# 02_POWER_SUPPLY_USB.net
KiCad netlist of a schematic drawn in Altium Designer
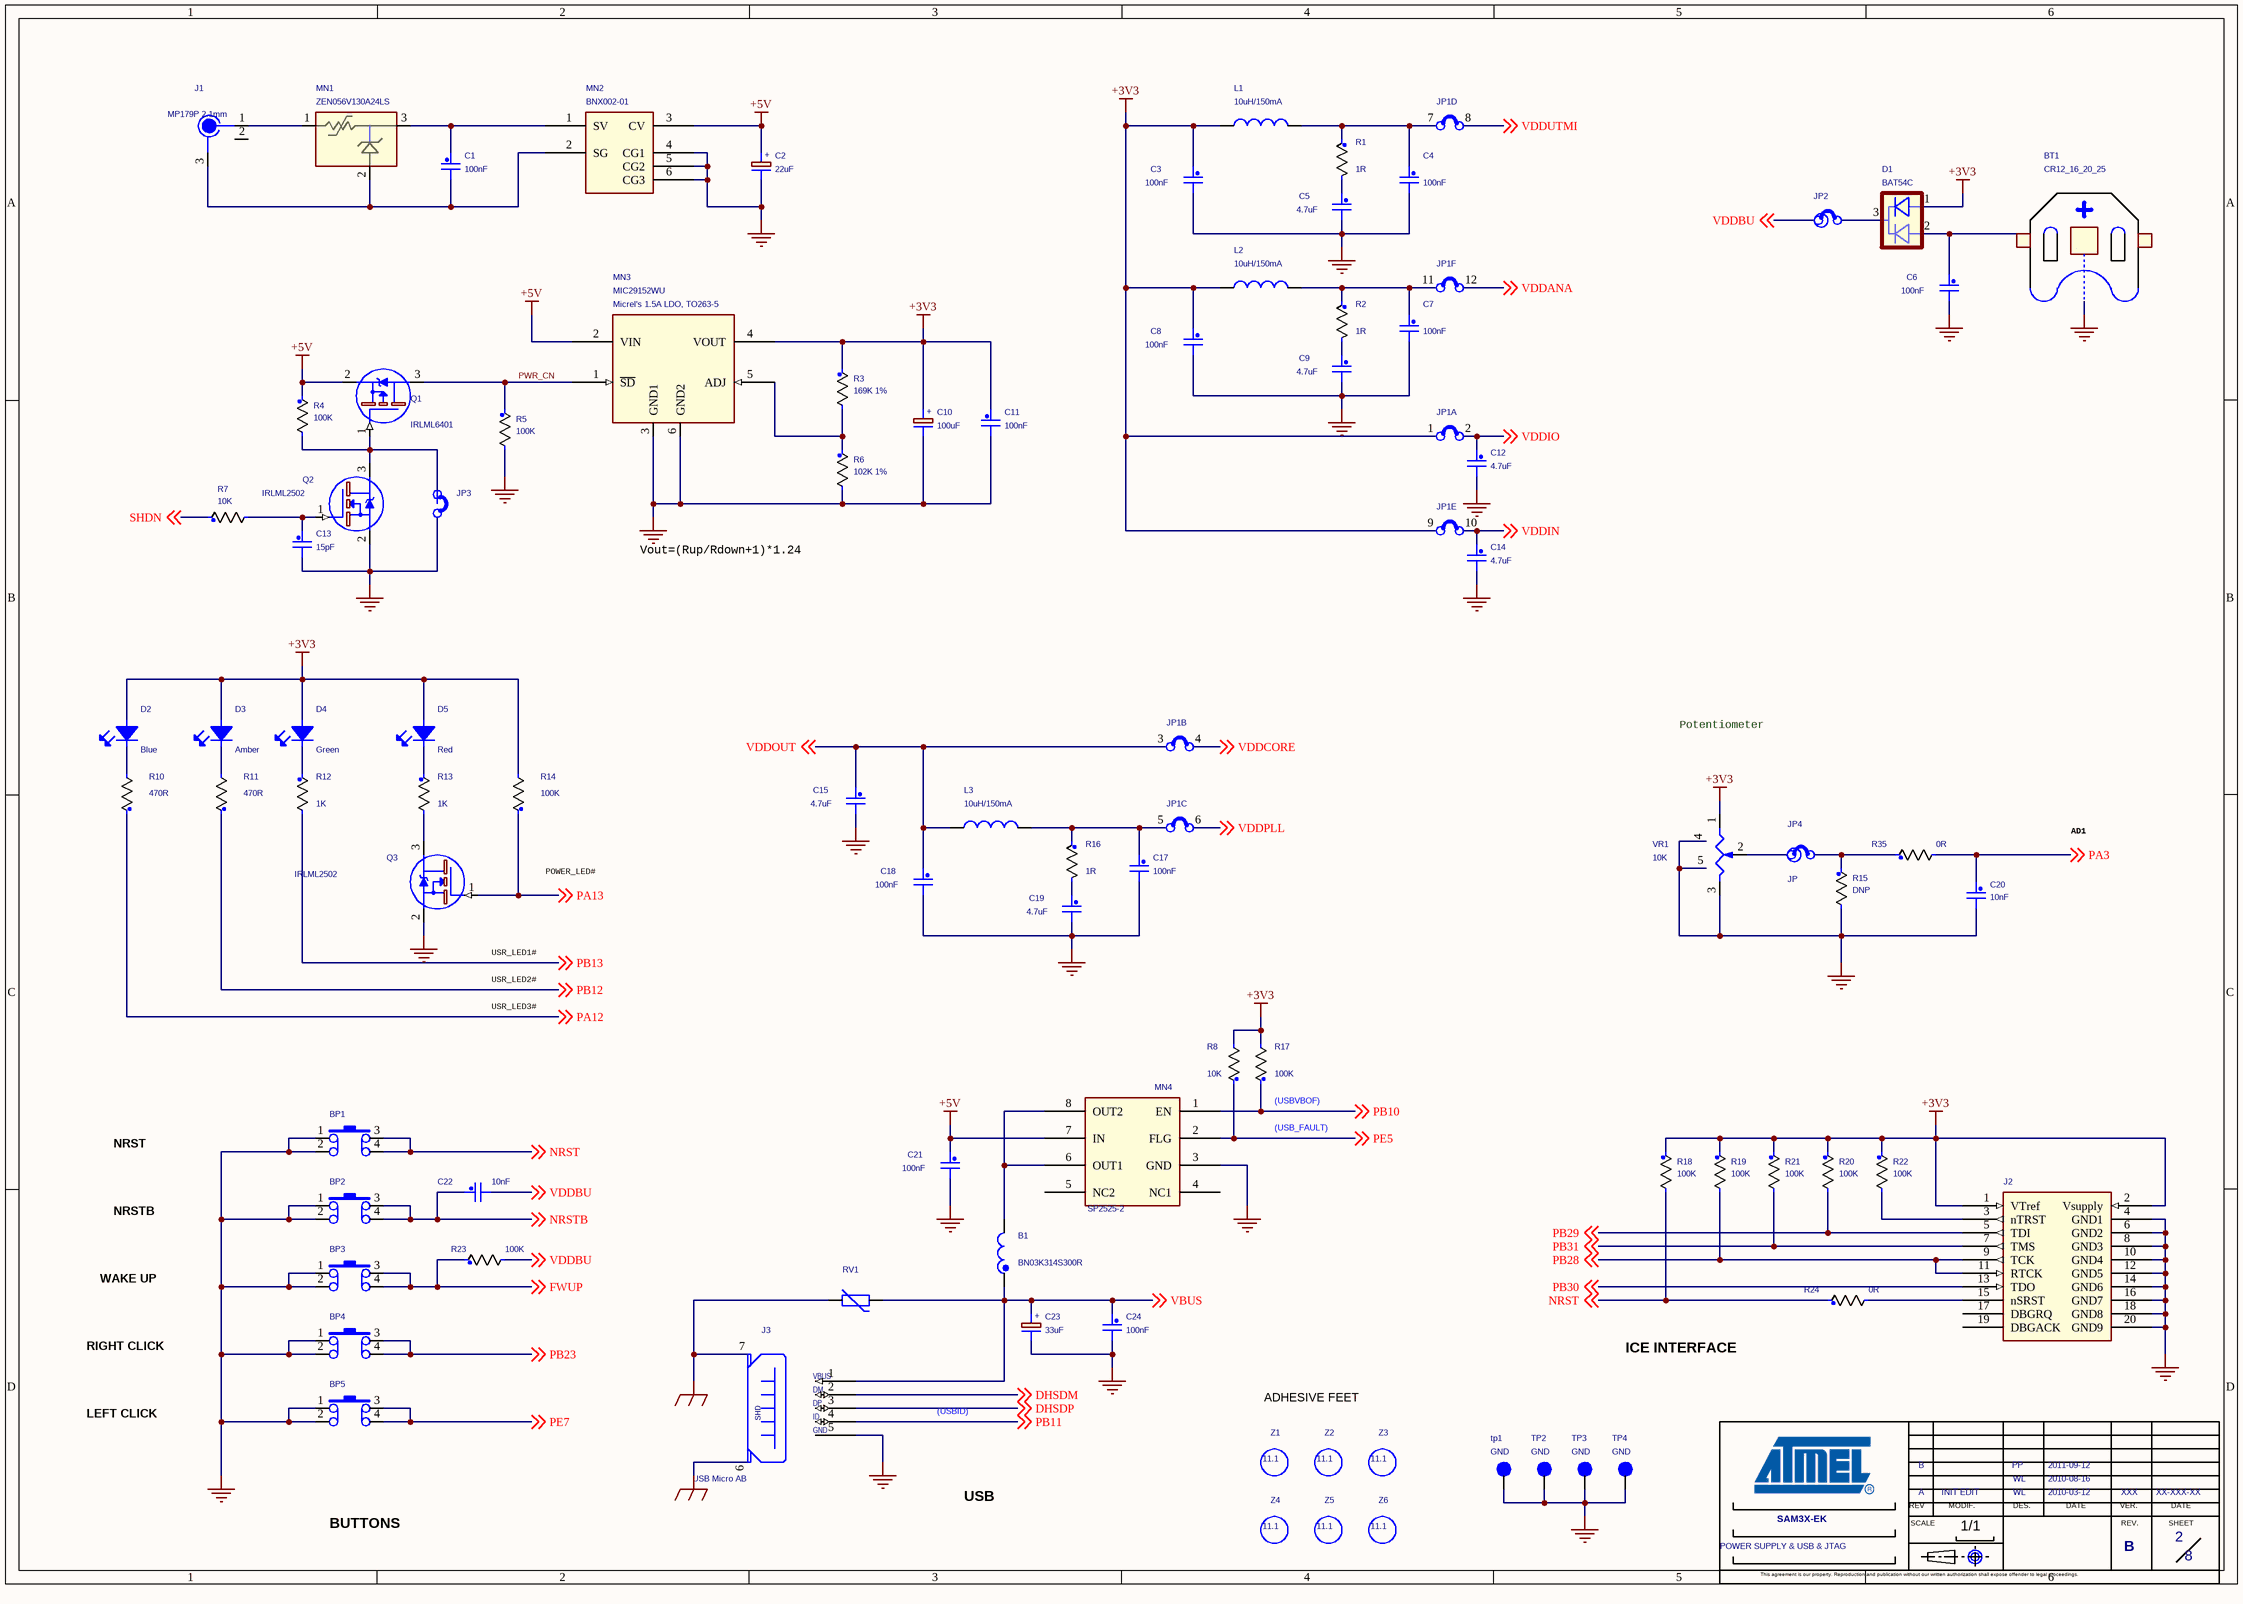
[diagram p0: 02_POWER SUPPLY & USB &.SchDoc]

(export (version "E")
  (design (tool "Eeschema 10.0.6"))
  (components
    (comp (ref "B1") (value "BN03K314S300R") (footprint "R0603") (libsource (lib "*") (part "BEAD")))
    (comp (ref "BP1") (value "T062") (footprint "KEY") (libsource (lib "*") (part "B3S_2")))
    (comp (ref "BP2") (value "T062") (footprint "KEY") (libsource (lib "*") (part "B3S_2")))
    (comp (ref "BP3") (value "T062") (footprint "KEY") (libsource (lib "*") (part "B3S_2")))
    (comp (ref "BP4") (value "T062") (footprint "KEY") (libsource (lib "*") (part "B3S_2")))
    (comp (ref "BP5") (value "T062") (footprint "KEY") (libsource (lib "*") (part "B3S_2")))
    (comp (ref "BT1")
      (value "CR12_16_20_25")
      (footprint "x-s_3000_01")
      (fields (field (name "PART NUMBER") "3UQTVB-18"))
      (libsource (lib "*") (part "Battery Holder CR12_16_20_25"))
    )
    (comp (ref "C1")
      (value "100nF")
      (footprint "CAP0805")
      (fields (field (name "VOLTAGE") "16V"))
      (libsource (lib "*") (part "C_Generic"))
    )
    (comp (ref "C2") (value "22uF") (footprint "C3528-21") (libsource (lib "*") (part "CAP_PN")))
    (comp (ref "C3")
      (value "100nF")
      (footprint "CAP0805")
      (fields (field (name "VOLTAGE") "16V"))
      (libsource (lib "*") (part "C_Generic"))
    )
    (comp (ref "C4")
      (value "100nF")
      (footprint "CAP0805")
      (fields (field (name "VOLTAGE") "16V"))
      (libsource (lib "*") (part "C_Generic"))
    )
    (comp (ref "C5")
      (value "4.7uF")
      (footprint "CAP0805")
      (fields (field (name "VOLTAGE") "16V"))
      (libsource (lib "*") (part "C_Generic"))
    )
    (comp (ref "C6")
      (value "100nF")
      (footprint "CAP0805")
      (fields (field (name "VOLTAGE") "16V"))
      (libsource (lib "*") (part "C_Generic"))
    )
    (comp (ref "C7")
      (value "100nF")
      (footprint "CAP0805")
      (fields (field (name "VOLTAGE") "16V"))
      (libsource (lib "*") (part "C_Generic"))
    )
    (comp (ref "C8")
      (value "100nF")
      (footprint "CAP0805")
      (fields (field (name "VOLTAGE") "16V"))
      (libsource (lib "*") (part "C_Generic"))
    )
    (comp (ref "C9")
      (value "4.7uF")
      (footprint "CAP0805")
      (fields (field (name "VOLTAGE") "16V"))
      (libsource (lib "*") (part "C_Generic"))
    )
    (comp (ref "C10") (value "100uF") (footprint "C3528-21") (libsource (lib "*") (part "CAP_PN")))
    (comp (ref "C11")
      (value "100nF")
      (footprint "CAP0805")
      (fields (field (name "VOLTAGE") "16V"))
      (libsource (lib "*") (part "C_Generic"))
    )
    (comp (ref "C12")
      (value "4.7uF")
      (footprint "CAP0805")
      (fields (field (name "VOLTAGE") "16V"))
      (libsource (lib "*") (part "C_Generic"))
    )
    (comp (ref "C13")
      (value "15pF")
      (footprint "CAP0805")
      (fields (field (name "VOLTAGE") "50V"))
      (libsource (lib "*") (part "C_Generic"))
    )
    (comp (ref "C14")
      (value "4.7uF")
      (footprint "CAP0805")
      (fields (field (name "VOLTAGE") "16V"))
      (libsource (lib "*") (part "C_Generic"))
    )
    (comp (ref "C15")
      (value "4.7uF")
      (footprint "CAP0805")
      (fields (field (name "VOLTAGE") "16V"))
      (libsource (lib "*") (part "C_Generic"))
    )
    (comp (ref "C17")
      (value "100nF")
      (footprint "CAP0805")
      (fields (field (name "VOLTAGE") "16V"))
      (libsource (lib "*") (part "C_Generic"))
    )
    (comp (ref "C18")
      (value "100nF")
      (footprint "CAP0805")
      (fields (field (name "VOLTAGE") "16V"))
      (libsource (lib "*") (part "C_Generic"))
    )
    (comp (ref "C19")
      (value "4.7uF")
      (footprint "CAP0805")
      (fields (field (name "VOLTAGE") "16V"))
      (libsource (lib "*") (part "C_Generic"))
    )
    (comp (ref "C20")
      (value "10nF")
      (footprint "CAP0805")
      (fields (field (name "VOLTAGE") "16V"))
      (libsource (lib "*") (part "C_Generic"))
    )
    (comp (ref "C21")
      (value "100nF")
      (footprint "CAP0805")
      (fields (field (name "VOLTAGE") "16V"))
      (libsource (lib "*") (part "C_Generic"))
    )
    (comp (ref "C22")
      (value "10nF")
      (footprint "CAP0805")
      (fields (field (name "VOLTAGE") "16V"))
      (libsource (lib "*") (part "C_Generic"))
    )
    (comp (ref "C23") (value "33uF") (footprint "C3528-21") (libsource (lib "*") (part "CAP_PN")))
    (comp (ref "C24")
      (value "100nF")
      (footprint "CAP0805")
      (fields (field (name "VOLTAGE") "16V"))
      (libsource (lib "*") (part "C_Generic"))
    )
    (comp (ref "D1") (value "BAT54C") (footprint "SOT-23") (libsource (lib "*") (part "BAT54C")))
    (comp (ref "D2") (value "Blue") (footprint "LED0805") (libsource (lib "*") (part "LED_Small_1")))
    (comp (ref "D3") (value "Amber") (footprint "LED0805") (libsource (lib "*") (part "LED_Small_1")))
    (comp (ref "D4") (value "Green") (footprint "LED0805") (libsource (lib "*") (part "LED_Small_1")))
    (comp (ref "D5") (value "Red") (footprint "LED0805") (libsource (lib "*") (part "LED_Small_1")))
    (comp (ref "J1")
      (value "Jack MP179P 2.1mm")
      (footprint "CONNECT3PTS03")
      (fields (field (name "VAL") "MP179P 2.1mm"))
      (libsource (lib "*") (part "Jack"))
    )
    (comp (ref "J2") (value "IDC20-2.54mm") (footprint "20PIN2") (libsource (lib "*") (part "JTAG")))
    (comp (ref "J3")
      (value "USB Micro AB")
      (footprint "usb_micro_ab")
      (description "CON,USB Micro B")
      (fields (field (name "MANUFACTURER PART NUMBER") "1981568-1") (field (name "MANUFACTURER") "Tyco"))
      (libsource (lib "*") (part "USB_MicroAB"))
    )
    (comp (ref "JP1")
      (value "SMT_JUMPER")
      (footprint "jms_tsm-2x6pts")
      (libsource (lib "*") (part "SMT_JUMPER"))
    )
    (comp (ref "JP2") (value "JP") (footprint "BAR2PTS02") (libsource (lib "*") (part "JUMP_0")))
    (comp (ref "JP3") (value "JP") (footprint "BAR2PTS02") (libsource (lib "*") (part "JUMP_0")))
    (comp (ref "JP4") (value "JP") (footprint "BAR2PTS02") (libsource (lib "*") (part "JUMP_0")))
    (comp (ref "L1") (value "10uH/150mA") (footprint "NLFV25T") (libsource (lib "*") (part "L_0")))
    (comp (ref "L2") (value "10uH/150mA") (footprint "NLFV25T") (libsource (lib "*") (part "L_0")))
    (comp (ref "L3") (value "10uH/150mA") (footprint "NLFV25T") (libsource (lib "*") (part "L_0")))
    (comp (ref "MN1") (value "ZEN056V130A24LS") (footprint "POLYZEN") (libsource (lib "*") (part "ZEN056")))
    (comp (ref "MN2") (value "BNX002-01") (footprint "BNX001") (libsource (lib "*") (part "BNX002_01")))
    (comp (ref "MN3")
      (value "MIC29152WU")
      (footprint "ADI/SM/TO263/5")
      (fields (field (name "NOTE") "Micrel's 1.5A LDO, TO263-5"))
      (libsource (lib "*") (part "LP3965ES_ADJ"))
    )
    (comp (ref "MN4") (value "SP2525-2") (footprint "NSOIC8") (libsource (lib "*") (part "SP2525-SO8_1")))
    (comp (ref "Q1")
      (value "IRLML6401")
      (footprint "SOT23T02")
      (fields (field (name "REF") "IRLML6401"))
      (libsource (lib "*") (part "IRLML6302"))
    )
    (comp (ref "Q2")
      (value "IRLML2502")
      (footprint "SOT23T02")
      (fields (field (name "VAL") "IRLML2502"))
      (libsource (lib "") (part "IRLML2402_1"))
    )
    (comp (ref "Q3")
      (value "IRLML2502")
      (footprint "SOT23T02")
      (fields (field (name "VAL") "IRLML2502"))
      (libsource (lib "*") (part "IRLML2402"))
    )
    (comp (ref "R1") (value "1R") (footprint "R0603") (libsource (lib "*") (part "R_Generic")))
    (comp (ref "R2") (value "1R") (footprint "R0603") (libsource (lib "*") (part "R_Generic")))
    (comp (ref "R3") (value "169K 1%") (footprint "r0603") (libsource (lib "*") (part "R_Generic")))
    (comp (ref "R4") (value "100K") (footprint "R0603") (libsource (lib "*") (part "R_Generic")))
    (comp (ref "R5") (value "100K") (footprint "R0603") (libsource (lib "*") (part "R_Generic")))
    (comp (ref "R6") (value "102K 1%") (footprint "r0603") (libsource (lib "*") (part "R_Generic")))
    (comp (ref "R7") (value "10K") (footprint "R0603") (libsource (lib "*") (part "R_Generic")))
    (comp (ref "R8") (value "10K") (footprint "R0603") (libsource (lib "*") (part "R_Generic")))
    (comp (ref "R10") (value "470R") (footprint "R0603") (libsource (lib "*") (part "R_Generic")))
    (comp (ref "R11") (value "470R") (footprint "R0603") (libsource (lib "*") (part "R_Generic")))
    (comp (ref "R12") (value "1K") (footprint "r0603") (libsource (lib "*") (part "R_Generic")))
    (comp (ref "R13") (value "1K") (footprint "r0603") (libsource (lib "*") (part "R_Generic")))
    (comp (ref "R14") (value "100K") (footprint "R0603") (libsource (lib "*") (part "R_Generic")))
    (comp (ref "R15") (value "DNP") (footprint "R0603") (libsource (lib "*") (part "R_Generic")))
    (comp (ref "R16") (value "1R") (footprint "R0603") (libsource (lib "*") (part "R_Generic")))
    (comp (ref "R17") (value "100K") (footprint "R0603") (libsource (lib "*") (part "R_Generic")))
    (comp (ref "R18") (value "100K") (footprint "r0603") (libsource (lib "*") (part "R_Generic")))
    (comp (ref "R19") (value "100K") (footprint "r0603") (libsource (lib "*") (part "R_Generic")))
    (comp (ref "R20") (value "100K") (footprint "r0603") (libsource (lib "*") (part "R_Generic")))
    (comp (ref "R21") (value "100K") (footprint "r0603") (libsource (lib "*") (part "R_Generic")))
    (comp (ref "R22") (value "100K") (footprint "r0603") (libsource (lib "*") (part "R_Generic")))
    (comp (ref "R23") (value "100K") (footprint "R0603") (libsource (lib "*") (part "R_Generic")))
    (comp (ref "R24") (value "0R") (footprint "r0603") (libsource (lib "*") (part "R_Generic")))
    (comp (ref "R35") (value "0R") (footprint "r0603") (libsource (lib "*") (part "R_Generic")))
    (comp (ref "RV1")
      (value "VARISTOR_0603")
      (footprint "R0603")
      (libsource (lib "*") (part "VARISTOR_0603"))
    )
    (comp (ref "SH1")
      (value "Jumper Pitch 2.54")
      (footprint "JUMPER-2.54")
      (description "Jumper,2 Points Jumper Pitch 2.54")
      (fields (field (name "PART NUMBER") "440-00002-1") (field (name "MANUFACTURER") "WIESON"))
      (libsource (lib "") (part "JUMPER-2.54_1"))
    )
    (comp (ref "SH2")
      (value "Jumper Pitch 2.54")
      (footprint "JUMPER-2.54")
      (description "Jumper,2 Points Jumper Pitch 2.54")
      (fields (field (name "PART NUMBER") "440-00002-1") (field (name "MANUFACTURER") "WIESON"))
      (libsource (lib "*") (part "JUMPER-2.54"))
    )
    (comp (ref "SH3")
      (value "Jumper Pitch 2.54")
      (footprint "JUMPER-2.54")
      (description "Jumper,2 Points Jumper Pitch 2.54")
      (fields (field (name "PART NUMBER") "440-00002-1") (field (name "MANUFACTURER") "WIESON"))
      (libsource (lib "") (part "JUMPER-2.54_1"))
    )
    (comp (ref "SH4")
      (value "Jumper Pitch 2.54")
      (footprint "JUMPER-2.54")
      (description "Jumper,2 Points Jumper Pitch 2.54")
      (fields
        (field (name "MANUFACTURER PART NUMBER") "G4160-1A60BF1U")
        (field (name "MANUFACTURER") "WIESON")
      )
      (libsource (lib "") (part "JUMPER-2.54_1"))
    )
    (comp (ref "SH5")
      (value "Jumper Pitch 2.54")
      (footprint "JUMPER-2.54")
      (description "Jumper,2 Points Jumper Pitch 2.54")
      (fields (field (name "PART NUMBER") "440-00002-1") (field (name "MANUFACTURER") "WIESON"))
      (libsource (lib "") (part "JUMPER-2.54_1"))
    )
    (comp (ref "SH6")
      (value "Jumper Pitch 2.54")
      (footprint "JUMPER-2.54")
      (description "Jumper,2 Points Jumper Pitch 2.54")
      (fields (field (name "PART NUMBER") "440-00002-1") (field (name "MANUFACTURER") "WIESON"))
      (libsource (lib "") (part "JUMPER-2.54_1"))
    )
    (comp (ref "SH8")
      (value "Jumper Pitch 2.54")
      (footprint "JUMPER-2.54")
      (description "Jumper,2 Points Jumper Pitch 2.54")
      (fields (field (name "PART NUMBER") "440-00002-1") (field (name "MANUFACTURER") "WIESON"))
      (libsource (lib "") (part "JUMPER-2.54_1"))
    )
    (comp (ref "SH9")
      (value "Jumper Pitch 2.54")
      (footprint "JUMPER-2.54")
      (description "Jumper,2 Points Jumper Pitch 2.54")
      (fields
        (field (name "MANUFACTURER PART NUMBER") "G4160-1A60BF1U")
        (field (name "MANUFACTURER") "WIESON")
      )
      (libsource (lib "*") (part "JUMPER-2.54"))
    )
    (comp (ref "SH10")
      (value "Jumper Pitch 2.54")
      (footprint "JUMPER-2.54")
      (description "Jumper,2 Points Jumper Pitch 2.54")
      (fields (field (name "PART NUMBER") "440-00002-1") (field (name "MANUFACTURER") "WIESON"))
      (libsource (lib "") (part "JUMPER-2.54_1"))
    )
    (comp (ref "tp1") (value "GND") (footprint "KST5012") (libsource (lib "*") (part "TP")))
    (comp (ref "TP2") (value "GND") (footprint "KST5012") (libsource (lib "*") (part "TP")))
    (comp (ref "TP3") (value "GND") (footprint "KST5012") (libsource (lib "*") (part "TP")))
    (comp (ref "TP4") (value "GND") (footprint "KST5012") (libsource (lib "*") (part "TP")))
    (comp (ref "VR1") (value "10K") (footprint "POT_3") (libsource (lib "*") (part "POT2")))
    (comp (ref "Z1")
      (value "11.1")
      (footprint "TM6CIR3_2")
      (libsource (lib "*") (part "PIED ADHESIF 11.1mm"))
    )
    (comp (ref "Z2")
      (value "11.1")
      (footprint "TM6CIR3_2")
      (libsource (lib "*") (part "PIED ADHESIF 11.1mm"))
    )
    (comp (ref "Z3")
      (value "11.1")
      (footprint "TM6CIR3_2")
      (libsource (lib "*") (part "PIED ADHESIF 11.1mm"))
    )
    (comp (ref "Z4")
      (value "11.1")
      (footprint "TM6CIR3_2")
      (libsource (lib "*") (part "PIED ADHESIF 11.1mm"))
    )
    (comp (ref "Z5")
      (value "11.1")
      (footprint "TM6CIR3_2")
      (libsource (lib "*") (part "PIED ADHESIF 11.1mm"))
    )
    (comp (ref "Z6")
      (value "11.1")
      (footprint "TM6CIR3_2")
      (libsource (lib "*") (part "PIED ADHESIF 11.1mm"))
    )
  )
  (nets
    (net (code "1") (name "+3V3") (class "Default")
      (node (ref "C10") (pin "1") (pinfunction "1_1") (pintype "passive"))
      (node (ref "C11") (pin "1") (pinfunction "1_1") (pintype "passive"))
      (node (ref "C3") (pin "1") (pinfunction "1_1") (pintype "passive"))
      (node (ref "C8") (pin "1") (pinfunction "1_1") (pintype "passive"))
      (node (ref "D1") (pin "1") (pinfunction "K_1") (pintype "passive"))
      (node (ref "D2") (pin "1") (pinfunction "A_1") (pintype "passive"))
      (node (ref "D3") (pin "1") (pinfunction "A_1") (pintype "passive"))
      (node (ref "D4") (pin "1") (pinfunction "A_1") (pintype "passive"))
      (node (ref "D5") (pin "1") (pinfunction "A_1") (pintype "passive"))
      (node (ref "J2") (pin "1") (pinfunction "VTref_1") (pintype "input"))
      (node (ref "J2") (pin "2") (pinfunction "Vsupply_2") (pintype "input"))
      (node (ref "JP1") (pin "1") (pinfunction "1_1") (pintype "passive"))
      (node (ref "JP1") (pin "9") (pinfunction "9_9") (pintype "passive"))
      (node (ref "L1") (pin "2") (pinfunction "2_2") (pintype "passive"))
      (node (ref "L2") (pin "2") (pinfunction "2_2") (pintype "passive"))
      (node (ref "MN3") (pin "4") (pinfunction "VOUT_4") (pintype "power_in"))
      (node (ref "R14") (pin "2") (pinfunction "2_2") (pintype "passive"))
      (node (ref "R17") (pin "2") (pinfunction "2_2") (pintype "passive"))
      (node (ref "R18") (pin "1") (pinfunction "1_1") (pintype "passive"))
      (node (ref "R19") (pin "1") (pinfunction "1_1") (pintype "passive"))
      (node (ref "R20") (pin "1") (pinfunction "1_1") (pintype "passive"))
      (node (ref "R21") (pin "1") (pinfunction "1_1") (pintype "passive"))
      (node (ref "R22") (pin "1") (pinfunction "1_1") (pintype "passive"))
      (node (ref "R3") (pin "1") (pinfunction "1_1") (pintype "passive"))
      (node (ref "R8") (pin "2") (pinfunction "2_2") (pintype "passive"))
      (node (ref "VR1") (pin "1") (pinfunction "1_1") (pintype "passive"))
    )
    (net (code "2") (name "+5V") (class "Default")
      (node (ref "C2") (pin "1") (pinfunction "1_1") (pintype "passive"))
      (node (ref "C21") (pin "1") (pinfunction "1_1") (pintype "passive"))
      (node (ref "MN2") (pin "3") (pinfunction "CV_3") (pintype "passive"))
      (node (ref "MN3") (pin "2") (pinfunction "VIN_2") (pintype "power_in"))
      (node (ref "MN4") (pin "7") (pinfunction "IN_7") (pintype "power_in"))
      (node (ref "Q1") (pin "2") (pinfunction "S_2") (pintype "passive"))
      (node (ref "R4") (pin "1") (pinfunction "1_1") (pintype "passive"))
    )
    (net (code "3") (name "/PWR_CN") (class "Default")
      (node (ref "MN3") (pin "1") (pinfunction "~{SD}_1") (pintype "input"))
      (node (ref "Q1") (pin "3") (pinfunction "D_3") (pintype "open_collector"))
      (node (ref "R5") (pin "1") (pinfunction "1_1") (pintype "passive"))
    )
    (net (code "4") (name "DHSDM") (class "Default")
      (node (ref "J3") (pin "2") (pinfunction "DM_2") (pintype "bidirectional"))
    )
    (net (code "5") (name "DHSDP") (class "Default")
      (node (ref "J3") (pin "3") (pinfunction "DP_3") (pintype "bidirectional"))
    )
    (net (code "6") (name "FWUP") (class "Default")
      (node (ref "BP3") (pin "3") (pinfunction "T3_3") (pintype "passive"))
      (node (ref "BP3") (pin "4") (pinfunction "T4_4") (pintype "passive"))
      (node (ref "R23") (pin "1") (pinfunction "1_1") (pintype "passive"))
    )
    (net (code "7") (name "GND_EARTH") (class "Default")
      (node (ref "J3") (pin "6") (pinfunction "SH1_6") (pintype "passive"))
      (node (ref "J3") (pin "7") (pinfunction "SH2_7") (pintype "passive"))
      (node (ref "RV1") (pin "1") (pinfunction "1_1") (pintype "passive"))
    )
    (net (code "8") (name "GND_POWER") (class "Default")
      (node (ref "BP1") (pin "1") (pinfunction "T1_1") (pintype "passive"))
      (node (ref "BP1") (pin "2") (pinfunction "T2_2") (pintype "passive"))
      (node (ref "BP2") (pin "1") (pinfunction "T1_1") (pintype "passive"))
      (node (ref "BP2") (pin "2") (pinfunction "T2_2") (pintype "passive"))
      (node (ref "BP3") (pin "1") (pinfunction "T1_1") (pintype "passive"))
      (node (ref "BP3") (pin "2") (pinfunction "T2_2") (pintype "passive"))
      (node (ref "BP4") (pin "1") (pinfunction "T1_1") (pintype "passive"))
      (node (ref "BP4") (pin "2") (pinfunction "T2_2") (pintype "passive"))
      (node (ref "BP5") (pin "1") (pinfunction "T1_1") (pintype "passive"))
      (node (ref "BP5") (pin "2") (pinfunction "T2_2") (pintype "passive"))
      (node (ref "BT1") (pin "1") (pinfunction "M_1") (pintype "passive"))
      (node (ref "C10") (pin "2") (pinfunction "2_2") (pintype "passive"))
      (node (ref "C11") (pin "2") (pinfunction "2_2") (pintype "passive"))
      (node (ref "C12") (pin "2") (pinfunction "2_2") (pintype "passive"))
      (node (ref "C13") (pin "2") (pinfunction "2_2") (pintype "passive"))
      (node (ref "C14") (pin "2") (pinfunction "2_2") (pintype "passive"))
      (node (ref "C15") (pin "2") (pinfunction "2_2") (pintype "passive"))
      (node (ref "C17") (pin "2") (pinfunction "2_2") (pintype "passive"))
      (node (ref "C18") (pin "2") (pinfunction "2_2") (pintype "passive"))
      (node (ref "C19") (pin "2") (pinfunction "2_2") (pintype "passive"))
      (node (ref "C2") (pin "2") (pinfunction "2_2") (pintype "passive"))
      (node (ref "C20") (pin "2") (pinfunction "2_2") (pintype "passive"))
      (node (ref "C21") (pin "2") (pinfunction "2_2") (pintype "passive"))
      (node (ref "C23") (pin "2") (pinfunction "2_2") (pintype "passive"))
      (node (ref "C24") (pin "2") (pinfunction "2_2") (pintype "passive"))
      (node (ref "C3") (pin "2") (pinfunction "2_2") (pintype "passive"))
      (node (ref "C4") (pin "2") (pinfunction "2_2") (pintype "passive"))
      (node (ref "C5") (pin "2") (pinfunction "2_2") (pintype "passive"))
      (node (ref "C6") (pin "2") (pinfunction "2_2") (pintype "passive"))
      (node (ref "C7") (pin "2") (pinfunction "2_2") (pintype "passive"))
      (node (ref "C8") (pin "2") (pinfunction "2_2") (pintype "passive"))
      (node (ref "C9") (pin "2") (pinfunction "2_2") (pintype "passive"))
      (node (ref "J2") (pin "10") (pinfunction "GND4_10") (pintype "power_in"))
      (node (ref "J2") (pin "12") (pinfunction "GND5_12") (pintype "power_in"))
      (node (ref "J2") (pin "14") (pinfunction "GND6_14") (pintype "power_in"))
      (node (ref "J2") (pin "16") (pinfunction "GND7_16") (pintype "power_in"))
      (node (ref "J2") (pin "18") (pinfunction "GND8_18") (pintype "power_in"))
      (node (ref "J2") (pin "20") (pinfunction "GND9_20") (pintype "power_in"))
      (node (ref "J2") (pin "4") (pinfunction "GND1_4") (pintype "power_in"))
      (node (ref "J2") (pin "6") (pinfunction "GND2_6") (pintype "power_in"))
      (node (ref "J2") (pin "8") (pinfunction "GND3_8") (pintype "power_in"))
      (node (ref "J3") (pin "5") (pinfunction "GND_5") (pintype "power_in"))
      (node (ref "JP3") (pin "2") (pinfunction "2_2") (pintype "passive"))
      (node (ref "MN2") (pin "4") (pinfunction "CG1_4") (pintype "passive"))
      (node (ref "MN2") (pin "5") (pinfunction "CG2_5") (pintype "passive"))
      (node (ref "MN2") (pin "6") (pinfunction "CG3_6") (pintype "passive"))
      (node (ref "MN3") (pin "3") (pinfunction "GND1_3") (pintype "power_in"))
      (node (ref "MN3") (pin "6") (pinfunction "GND2_6") (pintype "power_in"))
      (node (ref "MN4") (pin "3") (pinfunction "GND_3") (pintype "passive"))
      (node (ref "Q2") (pin "2") (pinfunction "S_2") (pintype "passive"))
      (node (ref "Q3") (pin "2") (pinfunction "S_2") (pintype "passive"))
      (node (ref "R15") (pin "2") (pinfunction "2_2") (pintype "passive"))
      (node (ref "R5") (pin "2") (pinfunction "2_2") (pintype "passive"))
      (node (ref "R6") (pin "2") (pinfunction "2_2") (pintype "passive"))
      (node (ref "TP2") (pin "1") (pinfunction "TP_1") (pintype "passive"))
      (node (ref "TP3") (pin "1") (pinfunction "TP_1") (pintype "passive"))
      (node (ref "TP4") (pin "1") (pinfunction "TP_1") (pintype "passive"))
      (node (ref "VR1") (pin "3") (pinfunction "3_3") (pintype "passive"))
      (node (ref "VR1") (pin "4") (pinfunction "4_4") (pintype "passive"))
      (node (ref "VR1") (pin "5") (pinfunction "5_5") (pintype "passive"))
      (node (ref "tp1") (pin "1") (pinfunction "TP_1") (pintype "passive"))
    )
    (net (code "9") (name "NRST") (class "Default")
      (node (ref "BP1") (pin "3") (pinfunction "T3_3") (pintype "passive"))
      (node (ref "BP1") (pin "4") (pinfunction "T4_4") (pintype "passive"))
      (node (ref "R18") (pin "2") (pinfunction "2_2") (pintype "passive"))
      (node (ref "R24") (pin "1") (pinfunction "1_1") (pintype "passive"))
    )
    (net (code "10") (name "NRSTB") (class "Default")
      (node (ref "BP2") (pin "3") (pinfunction "T3_3") (pintype "passive"))
      (node (ref "BP2") (pin "4") (pinfunction "T4_4") (pintype "passive"))
      (node (ref "C22") (pin "1") (pinfunction "1_1") (pintype "passive"))
    )
    (net (code "11") (name "Net-(BT1-P1)") (class "Default")
      (node (ref "BT1") (pin "2") (pinfunction "P1_2") (pintype "passive"))
      (node (ref "C6") (pin "1") (pinfunction "1_1") (pintype "passive"))
      (node (ref "D1") (pin "2") (pinfunction "A_2") (pintype "passive"))
    )
    (net (code "12") (name "Net-(C4-Pad1)") (class "Default")
      (node (ref "C4") (pin "1") (pinfunction "1_1") (pintype "passive"))
      (node (ref "JP1") (pin "7") (pinfunction "7_7") (pintype "passive"))
      (node (ref "L1") (pin "1") (pinfunction "1_1") (pintype "passive"))
      (node (ref "R1") (pin "1") (pinfunction "1_1") (pintype "passive"))
    )
    (net (code "13") (name "Net-(C5-Pad1)") (class "Default")
      (node (ref "C5") (pin "1") (pinfunction "1_1") (pintype "passive"))
      (node (ref "R1") (pin "2") (pinfunction "2_2") (pintype "passive"))
    )
    (net (code "14") (name "Net-(C7-Pad1)") (class "Default")
      (node (ref "C7") (pin "1") (pinfunction "1_1") (pintype "passive"))
      (node (ref "JP1") (pin "11") (pinfunction "11_11") (pintype "passive"))
      (node (ref "L2") (pin "1") (pinfunction "1_1") (pintype "passive"))
      (node (ref "R2") (pin "1") (pinfunction "1_1") (pintype "passive"))
    )
    (net (code "15") (name "Net-(C9-Pad1)") (class "Default")
      (node (ref "C9") (pin "1") (pinfunction "1_1") (pintype "passive"))
      (node (ref "R2") (pin "2") (pinfunction "2_2") (pintype "passive"))
    )
    (net (code "16") (name "Net-(C17-Pad1)") (class "Default")
      (node (ref "C17") (pin "1") (pinfunction "1_1") (pintype "passive"))
      (node (ref "JP1") (pin "5") (pinfunction "5_5") (pintype "passive"))
      (node (ref "L3") (pin "1") (pinfunction "1_1") (pintype "passive"))
      (node (ref "R16") (pin "1") (pinfunction "1_1") (pintype "passive"))
    )
    (net (code "17") (name "Net-(C19-Pad1)") (class "Default")
      (node (ref "C19") (pin "1") (pinfunction "1_1") (pintype "passive"))
      (node (ref "R16") (pin "2") (pinfunction "2_2") (pintype "passive"))
    )
    (net (code "18") (name "Net-(D1-COM)") (class "Default")
      (node (ref "D1") (pin "3") (pinfunction "COM_3") (pintype "passive"))
      (node (ref "JP2") (pin "2") (pinfunction "2_2") (pintype "passive"))
    )
    (net (code "19") (name "Net-(D2-K)") (class "Default")
      (node (ref "D2") (pin "2") (pinfunction "K_2") (pintype "passive"))
      (node (ref "R10") (pin "2") (pinfunction "2_2") (pintype "passive"))
    )
    (net (code "20") (name "Net-(D3-K)") (class "Default")
      (node (ref "D3") (pin "2") (pinfunction "K_2") (pintype "passive"))
      (node (ref "R11") (pin "2") (pinfunction "2_2") (pintype "passive"))
    )
    (net (code "21") (name "Net-(D4-K)") (class "Default")
      (node (ref "D4") (pin "2") (pinfunction "K_2") (pintype "passive"))
      (node (ref "R12") (pin "1") (pinfunction "1_1") (pintype "passive"))
    )
    (net (code "22") (name "Net-(D5-K)") (class "Default")
      (node (ref "D5") (pin "2") (pinfunction "K_2") (pintype "passive"))
      (node (ref "R13") (pin "1") (pinfunction "1_1") (pintype "passive"))
    )
    (net (code "23") (name "Net-(J2-nSRST)") (class "Default")
      (node (ref "J2") (pin "15") (pinfunction "nSRST_15") (pintype "passive"))
      (node (ref "R24") (pin "2") (pinfunction "2_2") (pintype "passive"))
    )
    (net (code "24") (name "Net-(J2-nTRST)") (class "Default")
      (node (ref "J2") (pin "3") (pinfunction "nTRST_3") (pintype "output"))
      (node (ref "R22") (pin "2") (pinfunction "2_2") (pintype "passive"))
    )
    (net (code "25") (name "Net-(JP4-Pad1)") (class "Default")
      (node (ref "JP4") (pin "1") (pinfunction "1_1") (pintype "passive"))
      (node (ref "VR1") (pin "2") (pinfunction "2_2") (pintype "passive"))
    )
    (net (code "26") (name "Net-(JP4-Pad2)") (class "Default")
      (node (ref "JP4") (pin "2") (pinfunction "2_2") (pintype "passive"))
      (node (ref "R15") (pin "1") (pinfunction "1_1") (pintype "passive"))
      (node (ref "R35") (pin "1") (pinfunction "1_1") (pintype "passive"))
    )
    (net (code "27") (name "Net-(MN1-GND)") (class "Default")
      (node (ref "C1") (pin "2") (pinfunction "2_2") (pintype "passive"))
      (node (ref "J1") (pin "3") (pinfunction "3_3") (pintype "passive"))
      (node (ref "MN1") (pin "2") (pinfunction "GND_2") (pintype "passive"))
      (node (ref "MN2") (pin "2") (pinfunction "SG_2") (pintype "passive"))
    )
    (net (code "28") (name "Net-(MN1-VIN)") (class "Default")
      (node (ref "J1") (pin "1") (pinfunction "1_1") (pintype "passive"))
      (node (ref "MN1") (pin "1") (pinfunction "VIN_1") (pintype "passive"))
    )
    (net (code "29") (name "Net-(MN1-VOUT)") (class "Default")
      (node (ref "C1") (pin "1") (pinfunction "1_1") (pintype "passive"))
      (node (ref "MN1") (pin "3") (pinfunction "VOUT_3") (pintype "passive"))
      (node (ref "MN2") (pin "1") (pinfunction "SV_1") (pintype "passive"))
    )
    (net (code "30") (name "Net-(MN3-ADJ)") (class "Default")
      (node (ref "MN3") (pin "5") (pinfunction "ADJ_5") (pintype "input"))
      (node (ref "R3") (pin "2") (pinfunction "2_2") (pintype "passive"))
      (node (ref "R6") (pin "1") (pinfunction "1_1") (pintype "passive"))
    )
    (net (code "31") (name "Net-(MN4-OUT1)") (class "Default")
      (node (ref "B1") (pin "2") (pinfunction "2_2") (pintype "passive"))
      (node (ref "MN4") (pin "6") (pinfunction "OUT1_6") (pintype "passive"))
      (node (ref "MN4") (pin "8") (pinfunction "OUT2_8") (pintype "passive"))
    )
    (net (code "32") (name "Net-(Q1-G)") (class "Default")
      (node (ref "JP3") (pin "1") (pinfunction "1_1") (pintype "passive"))
      (node (ref "Q1") (pin "1") (pinfunction "G_1") (pintype "input"))
      (node (ref "Q2") (pin "3") (pinfunction "D_3") (pintype "open_collector"))
      (node (ref "R4") (pin "2") (pinfunction "2_2") (pintype "passive"))
    )
    (net (code "33") (name "Net-(Q2-G)") (class "Default")
      (node (ref "C13") (pin "1") (pinfunction "1_1") (pintype "passive"))
      (node (ref "Q2") (pin "1") (pinfunction "G_1") (pintype "input"))
      (node (ref "R7") (pin "2") (pinfunction "2_2") (pintype "passive"))
    )
    (net (code "34") (name "Net-(Q3-D)") (class "Default")
      (node (ref "Q3") (pin "3") (pinfunction "D_3") (pintype "open_collector"))
      (node (ref "R13") (pin "2") (pinfunction "2_2") (pintype "passive"))
    )
    (net (code "35") (name "PA3") (class "Default")
      (node (ref "C20") (pin "1") (pinfunction "1_1") (pintype "passive"))
      (node (ref "R35") (pin "2") (pinfunction "2_2") (pintype "passive"))
    )
    (net (code "36") (name "PA12") (class "Default")
      (node (ref "R10") (pin "1") (pinfunction "1_1") (pintype "passive"))
    )
    (net (code "37") (name "PA13") (class "Default")
      (node (ref "Q3") (pin "1") (pinfunction "G_1") (pintype "input"))
      (node (ref "R14") (pin "1") (pinfunction "1_1") (pintype "passive"))
    )
    (net (code "38") (name "PB10") (class "Default")
      (node (ref "MN4") (pin "1") (pinfunction "EN_1") (pintype "passive"))
      (node (ref "R17") (pin "1") (pinfunction "1_1") (pintype "passive"))
    )
    (net (code "39") (name "PB11") (class "Default")
      (node (ref "J3") (pin "4") (pinfunction "ID_4") (pintype "bidirectional"))
    )
    (net (code "40") (name "PB12") (class "Default")
      (node (ref "R11") (pin "1") (pinfunction "1_1") (pintype "passive"))
    )
    (net (code "41") (name "PB13") (class "Default")
      (node (ref "R12") (pin "2") (pinfunction "2_2") (pintype "passive"))
    )
    (net (code "42") (name "PB23") (class "Default")
      (node (ref "BP4") (pin "3") (pinfunction "T3_3") (pintype "passive"))
      (node (ref "BP4") (pin "4") (pinfunction "T4_4") (pintype "passive"))
    )
    (net (code "43") (name "PB28") (class "Default")
      (node (ref "J2") (pin "11") (pinfunction "RTCK_11") (pintype "input"))
      (node (ref "J2") (pin "9") (pinfunction "TCK_9") (pintype "output"))
      (node (ref "R19") (pin "2") (pinfunction "2_2") (pintype "passive"))
    )
    (net (code "44") (name "PB29") (class "Default")
      (node (ref "J2") (pin "5") (pinfunction "TDI_5") (pintype "output"))
      (node (ref "R20") (pin "2") (pinfunction "2_2") (pintype "passive"))
    )
    (net (code "45") (name "PB30") (class "Default")
      (node (ref "J2") (pin "13") (pinfunction "TDO_13") (pintype "input"))
    )
    (net (code "46") (name "PB31") (class "Default")
      (node (ref "J2") (pin "7") (pinfunction "TMS_7") (pintype "output"))
      (node (ref "R21") (pin "2") (pinfunction "2_2") (pintype "passive"))
    )
    (net (code "47") (name "PE5") (class "Default")
      (node (ref "MN4") (pin "2") (pinfunction "FLG_2") (pintype "passive"))
      (node (ref "R8") (pin "1") (pinfunction "1_1") (pintype "passive"))
    )
    (net (code "48") (name "PE7") (class "Default")
      (node (ref "BP5") (pin "3") (pinfunction "T3_3") (pintype "passive"))
      (node (ref "BP5") (pin "4") (pinfunction "T4_4") (pintype "passive"))
    )
    (net (code "49") (name "SHDN") (class "Default")
      (node (ref "R7") (pin "1") (pinfunction "1_1") (pintype "passive"))
    )
    (net (code "50") (name "VBUS") (class "Default")
      (node (ref "B1") (pin "1") (pinfunction "1_1") (pintype "passive"))
      (node (ref "C23") (pin "1") (pinfunction "1_1") (pintype "passive"))
      (node (ref "C24") (pin "1") (pinfunction "1_1") (pintype "passive"))
      (node (ref "J3") (pin "1") (pinfunction "VBUS_1") (pintype "input"))
      (node (ref "RV1") (pin "2") (pinfunction "2_2") (pintype "passive"))
    )
    (net (code "51") (name "VDDANA") (class "Default")
      (node (ref "JP1") (pin "12") (pinfunction "12_12") (pintype "passive"))
    )
    (net (code "52") (name "VDDBU") (class "Default")
      (node (ref "C22") (pin "2") (pinfunction "2_2") (pintype "passive"))
      (node (ref "JP2") (pin "1") (pinfunction "1_1") (pintype "passive"))
      (node (ref "R23") (pin "2") (pinfunction "2_2") (pintype "passive"))
    )
    (net (code "53") (name "VDDCORE") (class "Default")
      (node (ref "JP1") (pin "4") (pinfunction "4_4") (pintype "passive"))
    )
    (net (code "54") (name "VDDIN") (class "Default")
      (node (ref "C14") (pin "1") (pinfunction "1_1") (pintype "passive"))
      (node (ref "JP1") (pin "10") (pinfunction "10_10") (pintype "passive"))
    )
    (net (code "55") (name "VDDIO") (class "Default")
      (node (ref "C12") (pin "1") (pinfunction "1_1") (pintype "passive"))
      (node (ref "JP1") (pin "2") (pinfunction "2_2") (pintype "passive"))
    )
    (net (code "56") (name "VDDOUT") (class "Default")
      (node (ref "C15") (pin "1") (pinfunction "1_1") (pintype "passive"))
      (node (ref "C18") (pin "1") (pinfunction "1_1") (pintype "passive"))
      (node (ref "JP1") (pin "3") (pinfunction "3_3") (pintype "passive"))
      (node (ref "L3") (pin "2") (pinfunction "2_2") (pintype "passive"))
    )
    (net (code "57") (name "VDDPLL") (class "Default")
      (node (ref "JP1") (pin "6") (pinfunction "6_6") (pintype "passive"))
    )
    (net (code "58") (name "VDDUTMI") (class "Default")
      (node (ref "JP1") (pin "8") (pinfunction "8_8") (pintype "passive"))
    )
    (net (code "59") (name "unconnected-(BT1-P2-Pad3)") (class "Default")
      (node (ref "BT1") (pin "3") (pinfunction "P2_3") (pintype "passive"))
    )
    (net (code "60") (name "unconnected-(J1-Pad2)") (class "Default")
      (node (ref "J1") (pin "2") (pinfunction "2_2") (pintype "passive"))
    )
    (net (code "61") (name "unconnected-(J2-DBGACK-Pad19)") (class "Default")
      (node (ref "J2") (pin "19") (pinfunction "DBGACK_19") (pintype "passive"))
    )
    (net (code "62") (name "unconnected-(J2-DBGRQ-Pad17)") (class "Default")
      (node (ref "J2") (pin "17") (pinfunction "DBGRQ_17") (pintype "passive"))
    )
    (net (code "63") (name "unconnected-(MN4-NC1-Pad4)") (class "Default")
      (node (ref "MN4") (pin "4") (pinfunction "NC1_4") (pintype "passive"))
    )
    (net (code "64") (name "unconnected-(MN4-NC2-Pad5)") (class "Default")
      (node (ref "MN4") (pin "5") (pinfunction "NC2_5") (pintype "passive"))
    )
  )
)
